# Mechanical.net
KiCad netlist of a schematic drawn in Altium Designer
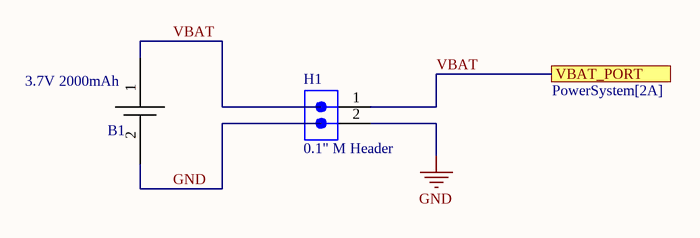
[diagram p0: Mechanical.SchDoc]

(export (version "E")
  (design (tool "Eeschema 10.0.6"))
  (components
    (comp (ref "B1")
      (value "3.7V 2000mAh")
      (footprint "2_PIN_100MIL_BATTERY")
      (description "Lithium Ion Battery - 3.7V 2000Mah Adafruit 2011")
      (fields
        (field (name "MANUFACTURER") "Adafruit Industries")
        (field (name "MANUFACTURER PART NUMBER") "2011")
      )
      (libsource (lib "SunflowerSCH") (part "2011_Battery"))
    )
    (comp (ref "H1")
      (value "0.1\" M Header")
      (footprint "2_PIN_100MIL")
      (description "CONN HEADER VERT 2POS 2.54MM")
      (fields
        (field (name "MANUFACTURER") "Sullins")
        (field (name "MANUFACTURER PART NUMBER") "PRPC002SAAN-RC")
      )
      (libsource (lib "SunflowerSCH") (part "Battery_2Pin_100mil"))
    )
  )
  (nets
    (net (code "1") (name "/VBAT") (class "Default")
      (node (ref "B1") (pin "1") (pinfunction "Power_1") (pintype "passive"))
      (node (ref "H1") (pin "1") (pinfunction "1_1") (pintype "passive"))
    )
    (net (code "2") (name "GND") (class "Default")
      (node (ref "B1") (pin "2") (pinfunction "Ground_2") (pintype "passive"))
      (node (ref "H1") (pin "2") (pinfunction "2_2") (pintype "passive"))
    )
  )
)
